# OMD_CAN_HORIZONTAL_dual.net
KiCad netlist of a schematic drawn in Altium Designer
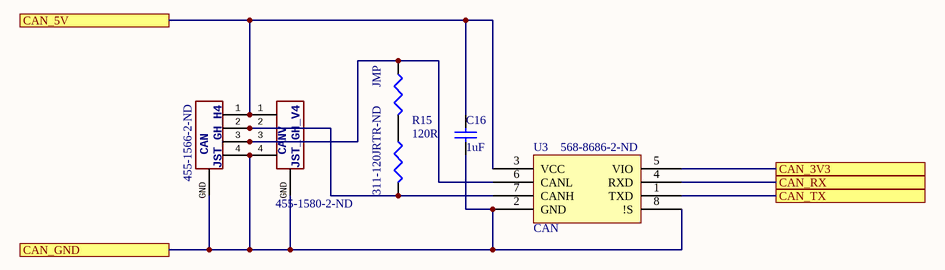
[diagram p0: OMD_CAN_HORIZONTAL_dual.SchDoc]

(export (version "E")
  (design (tool "Eeschema 10.0.6"))
  (components
    (comp (ref "C16")
      (value "1uF")
      (footprint "CAPC1005L")
      (description "CAP CER 1UF 6.3V X5R 0402")
      (fields (field (name "Comment") "Cap"))
      (libsource (lib "OMD") (part "Cap"))
    )
    (comp (ref "CAN")
      (value "JST_GH_H4")
      (footprint "JST_GH_H4")
      (description "SM04B-GHS-TB")
      (fields (field (name "SUPPLIER PART NUMBER 1") "455-1566-2-ND"))
      (libsource (lib "OMD") (part "JST_GH_H4"))
    )
    (comp (ref "CANV")
      (value "JST_GH_V4")
      (footprint "JST_GH_V4")
      (description "BM04B-GHS-TBT")
      (fields (field (name "SUPPLIER PART NUMBER 1") "455-1580-2-ND"))
      (libsource (lib "JST_GH") (part "JST_GH_V4"))
    )
    (comp (ref "JMP") (value "solder") (footprint "R0402") (libsource (lib "OMD") (part "Resistor")))
    (comp (ref "R15")
      (value "120R")
      (footprint "R0402")
      (description "RES SMD 120 OHM 5% 1/16W 0402")
      (fields (field (name "SUPPLIER PART NUMBER 1") "311-120JRTR-ND"))
      (libsource (lib "OMD") (part "Resistor"))
    )
    (comp (ref "U3")
      (value "CAN")
      (footprint "SON65P300X100_HS-9N")
      (fields (field (name "SUPPLIER PART NUMBER 1") "568-8686-2-ND"))
      (libsource (lib "OMD") (part "CAN"))
    )
  )
  (nets
    (net (code "1") (name "/CAN_3V3") (class "Default")
      (node (ref "U3") (pin "5") (pinfunction "VIO_5") (pintype "passive"))
    )
    (net (code "2") (name "/CAN_5V") (class "Default")
      (node (ref "C16") (pin "2") (pinfunction "2_2") (pintype "passive"))
      (node (ref "CAN") (pin "1") (pinfunction "1_1") (pintype "passive"))
      (node (ref "CANV") (pin "1") (pinfunction "1_1") (pintype "passive"))
      (node (ref "U3") (pin "3") (pinfunction "VCC_3") (pintype "passive"))
    )
    (net (code "3") (name "/CAN_GND") (class "Default")
      (node (ref "C16") (pin "1") (pinfunction "1_1") (pintype "passive"))
      (node (ref "CAN") (pin "4") (pinfunction "4_4") (pintype "passive"))
      (node (ref "CAN") (pin "GND") (pinfunction "GND_GND") (pintype "passive"))
      (node (ref "CANV") (pin "4") (pinfunction "4_4") (pintype "passive"))
      (node (ref "CANV") (pin "GND") (pinfunction "GND_GND") (pintype "passive"))
      (node (ref "U3") (pin "2") (pinfunction "GND_2") (pintype "passive"))
      (node (ref "U3") (pin "8") (pinfunction "!S_8") (pintype "passive"))
    )
    (net (code "4") (name "/CAN_RX") (class "Default")
      (node (ref "U3") (pin "4") (pinfunction "RXD_4") (pintype "passive"))
    )
    (net (code "5") (name "/CAN_TX") (class "Default")
      (node (ref "U3") (pin "1") (pinfunction "TXD_1") (pintype "passive"))
    )
    (net (code "6") (name "Net-(JMP-Pad2)") (class "Default")
      (node (ref "JMP") (pin "2") (pinfunction "2_2") (pintype "passive"))
      (node (ref "R15") (pin "1") (pinfunction "1_1") (pintype "passive"))
    )
    (net (code "7") (name "Net-(U3-CANH)") (class "Default")
      (node (ref "CAN") (pin "2") (pinfunction "2_2") (pintype "passive"))
      (node (ref "CANV") (pin "2") (pinfunction "2_2") (pintype "passive"))
      (node (ref "R15") (pin "2") (pinfunction "2_2") (pintype "passive"))
      (node (ref "U3") (pin "7") (pinfunction "CANH_7") (pintype "passive"))
    )
    (net (code "8") (name "Net-(U3-CANL)") (class "Default")
      (node (ref "CAN") (pin "3") (pinfunction "3_3") (pintype "passive"))
      (node (ref "CANV") (pin "3") (pinfunction "3_3") (pintype "passive"))
      (node (ref "JMP") (pin "1") (pinfunction "1_1") (pintype "passive"))
      (node (ref "U3") (pin "6") (pinfunction "CANL_6") (pintype "passive"))
    )
  )
)
